# NVME.net
KiCad netlist of a schematic drawn in Altium Designer
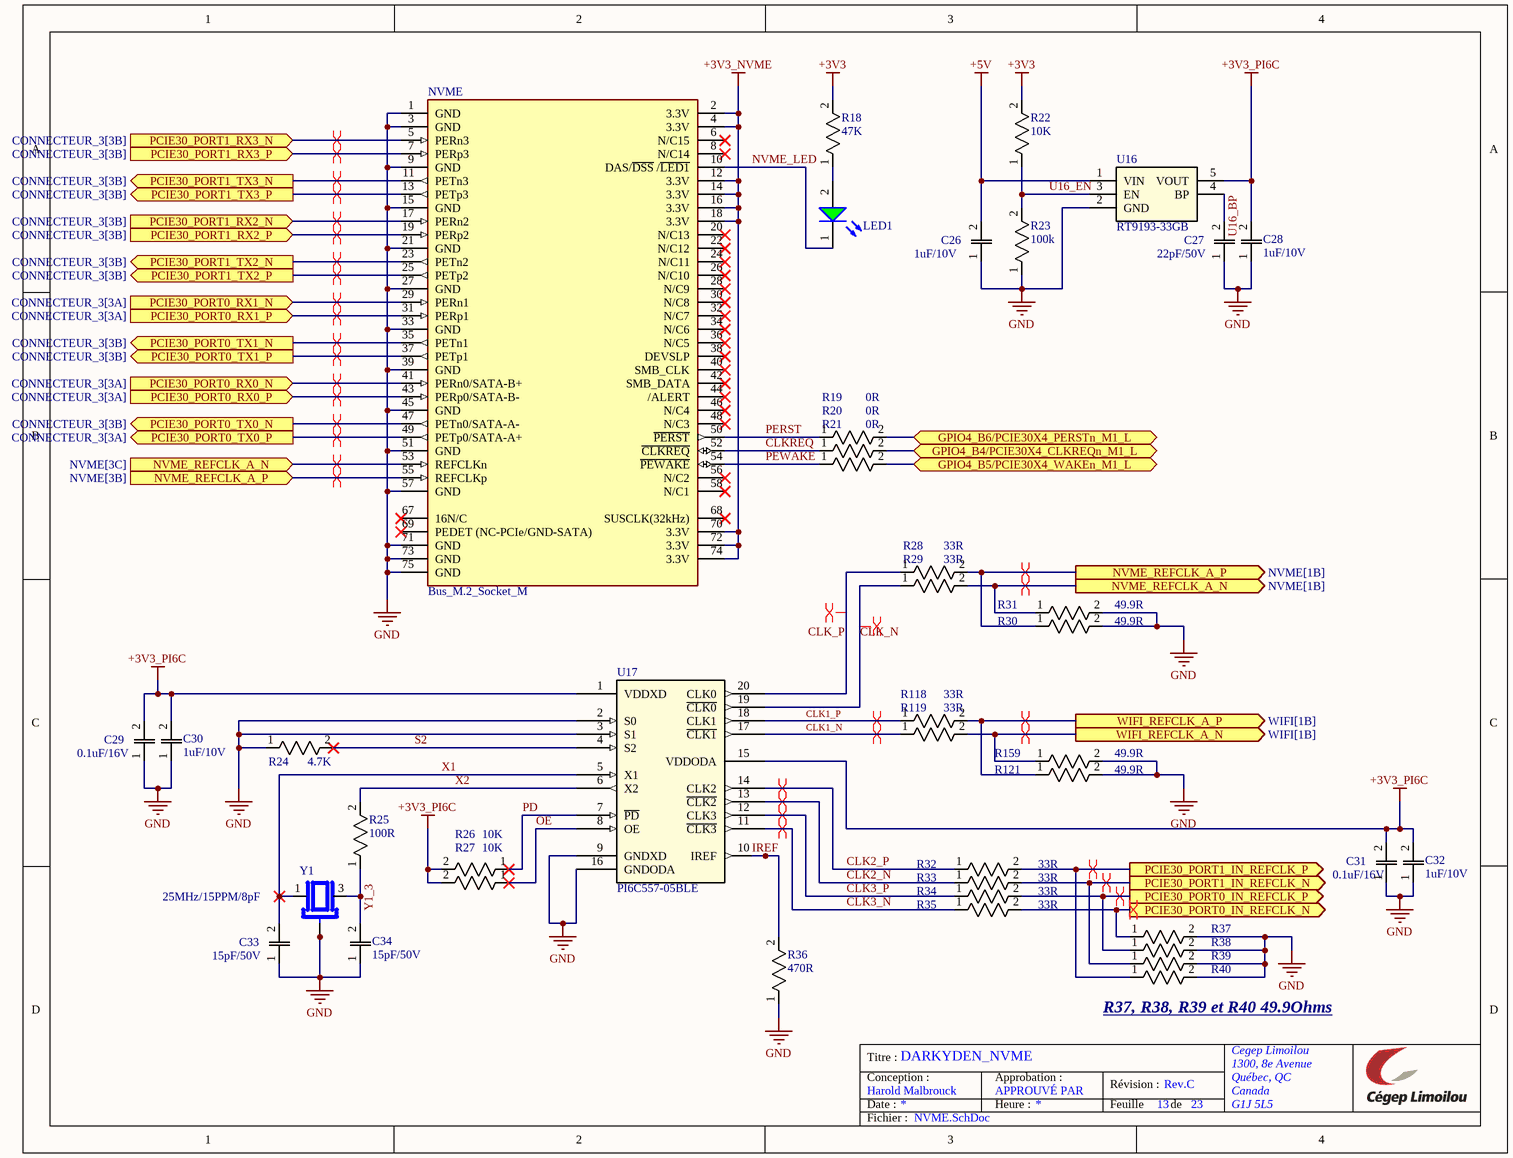
[diagram p0: NVME.SchDoc]

(export (version "E")
  (design (tool "Eeschema 10.0.6"))
  (components
    (comp (ref "C26")
      (value "1uF/10V")
      (footprint "C0805")
      (description "Multilayer Ceramic Capacitors MLCC - SMD/SMT 10V 1uF X7R 0805 10%")
      (fields
        (field (name "MANUFACTURER") "KEMET")
        (field (name "MANUFACTURER PART NUMBER") "C0805C105K8RACTU")
      )
      (libsource (lib "DARKYDEN") (part "C0805C105K8RACTU"))
    )
    (comp (ref "C27")
      (value "22pF/50V")
      (footprint "C0805")
      (description "Cap Ceramic 22pF 50V X7R 5% Pad SMD 0805 125°C T/R")
      (fields
        (field (name "MANUFACTURER") "KEMET")
        (field (name "MANUFACTURER PART NUMBER") "C0805C220J5RACTU")
      )
      (libsource (lib "DARKYDEN") (part "C0805C220J5RACTU"))
    )
    (comp (ref "C28")
      (value "1uF/10V")
      (footprint "C0805")
      (description "Multilayer Ceramic Capacitors MLCC - SMD/SMT 10V 1uF X7R 0805 10%")
      (fields
        (field (name "MANUFACTURER") "KEMET")
        (field (name "MANUFACTURER PART NUMBER") "C0805C105K8RACTU")
      )
      (libsource (lib "DARKYDEN") (part "C0805C105K8RACTU"))
    )
    (comp (ref "C29")
      (value "0.1uF/16V")
      (footprint "C0805")
      (description "0.1uF/16V ±10% X7R 0805 (2012METRIC) Ceramic Capacitor SMD Auto X7R")
      (fields
        (field (name "MANUFACTURER") "KEMET")
        (field (name "MANUFACTURER PART NUMBER") "C0805C104K4RACAUTO")
      )
      (libsource (lib "DARKYDEN") (part "C0805C104K4RACAUTO"))
    )
    (comp (ref "C30")
      (value "1uF/10V")
      (footprint "C0805")
      (description "Multilayer Ceramic Capacitors MLCC - SMD/SMT 10V 1uF X7R 0805 10%")
      (fields
        (field (name "MANUFACTURER") "KEMET")
        (field (name "MANUFACTURER PART NUMBER") "C0805C105K8RACTU")
      )
      (libsource (lib "DARKYDEN") (part "C0805C105K8RACTU"))
    )
    (comp (ref "C31")
      (value "0.1uF/16V")
      (footprint "C0805")
      (description "0.1uF/16V ±10% X7R 0805 (2012METRIC) Ceramic Capacitor SMD Auto X7R")
      (fields
        (field (name "MANUFACTURER") "KEMET")
        (field (name "MANUFACTURER PART NUMBER") "C0805C104K4RACAUTO")
      )
      (libsource (lib "DARKYDEN") (part "C0805C104K4RACAUTO"))
    )
    (comp (ref "C32")
      (value "1uF/10V")
      (footprint "C0805")
      (description "Multilayer Ceramic Capacitors MLCC - SMD/SMT 10V 1uF X7R 0805 10%")
      (fields
        (field (name "MANUFACTURER") "KEMET")
        (field (name "MANUFACTURER PART NUMBER") "C0805C105K8RACTU")
      )
      (libsource (lib "DARKYDEN") (part "C0805C105K8RACTU"))
    )
    (comp (ref "C33")
      (value "15pF/50V")
      (footprint "C0805")
      (description "Multilayer Ceramic Capacitors MLCC - SMD/SMT 50V 15pF X7R 0805 10% AEC-Q200")
      (fields
        (field (name "MANUFACTURER") "KEMET")
        (field (name "MANUFACTURER PART NUMBER") "C0805C150K5RACAUTO")
      )
      (libsource (lib "DARKYDEN") (part "C0805C150K5RACAUTO"))
    )
    (comp (ref "C34")
      (value "15pF/50V")
      (footprint "C0805")
      (description "Multilayer Ceramic Capacitors MLCC - SMD/SMT 50V 15pF X7R 0805 10% AEC-Q200")
      (fields
        (field (name "MANUFACTURER") "KEMET")
        (field (name "MANUFACTURER PART NUMBER") "C0805C150K5RACAUTO")
      )
      (libsource (lib "DARKYDEN") (part "C0805C150K5RACAUTO"))
    )
    (comp (ref "LED1")
      (value "Green, 3.2V, 140°")
      (footprint "WL-SMCD_0603")
      (description "WL-SMCD Mono-color Chip LED Diffused, SMT, size 0603, Green, 3.2V, 140°")
      (fields
        (field (name "MANUFACTURER PART NUMBER") "150060GS55040")
        (field (name "MANUFACTURER") "Wurth Elektronik")
      )
      (libsource (lib "0603_LED") (part "GREEN"))
    )
    (comp (ref "NVME")
      (value "Bus_M.2_Socket_M")
      (footprint "AMPHENOL_MDT420M03001")
      (fields (field (name "MF") "Amphenol Commercial") (field (name "MP") "MDT420M03001"))
      (libsource (lib "Bus_M.2_Socket_M") (part "Bus_M.2_Socket_M"))
    )
    (comp (ref "R18")
      (value "47K")
      (footprint "RESC1608X55N")
      (description "47K Ohm 5% 1/10W 0603 200ppm/C Molded SMD Punched Carrier T/R")
      (fields
        (field (name "MANUFACTURER") "Panasonic")
        (field (name "MANUFACTURER PART NUMBER") "ERJ-3GEYJ473V")
      )
      (libsource (lib "DARKYDEN") (part "ERJ-3GEYJ473V"))
    )
    (comp (ref "R19")
      (value "0R")
      (footprint "SamacSys:RESC1608X55N")
      (description "Zero Ohm Resistor, Jumper, 0603 [1608 Metric], Thick Film, 100 mW, 1 A, Surface Mount")
      (fields
        (field (name "MANUFACTURER_PART_NUMBER") "ERJ-3GEY0R00V")
        (field (name "MOUSER PART NUMBER") "667-ERJ-3GEY0R00V")
      )
      (libsource (lib "DARKYDEN") (part "ERJ-3GEY0R00V"))
    )
    (comp (ref "R20")
      (value "0R")
      (footprint "SamacSys:RESC1608X55N")
      (description "Zero Ohm Resistor, Jumper, 0603 [1608 Metric], Thick Film, 100 mW, 1 A, Surface Mount")
      (fields
        (field (name "MANUFACTURER_PART_NUMBER") "ERJ-3GEY0R00V")
        (field (name "MOUSER PART NUMBER") "667-ERJ-3GEY0R00V")
      )
      (libsource (lib "DARKYDEN") (part "ERJ-3GEY0R00V"))
    )
    (comp (ref "R21")
      (value "0R")
      (footprint "SamacSys:RESC1608X55N")
      (description "Zero Ohm Resistor, Jumper, 0603 [1608 Metric], Thick Film, 100 mW, 1 A, Surface Mount")
      (fields
        (field (name "MANUFACTURER_PART_NUMBER") "ERJ-3GEY0R00V")
        (field (name "MOUSER PART NUMBER") "667-ERJ-3GEY0R00V")
      )
      (libsource (lib "DARKYDEN") (part "ERJ-3GEY0R00V"))
    )
    (comp (ref "R22")
      (value "10K")
      (footprint "SamacSys:RESC1608X55N")
      (description "10K Ohm 5% Res Thick Film 0603  0.1W(1/10W) ±200ppm/C Pad SMD Automotive T/R")
      (fields
        (field (name "MANUFACTURER_PART_NUMBER") "ERJ-3GEYJ103V")
        (field (name "MOUSER PART NUMBER") "667-ERJ-3GEYJ103V")
      )
      (libsource (lib "DARKYDEN") (part "ERJ-3GEYJ103V"))
    )
    (comp (ref "R23")
      (value "100k")
      (footprint "SamacSys:RESC1608X55N")
      (description "100K Ohm 5%  Res Thick Film 0603 1/10W +/-200ppm/ßC Molded SMD Punched Carrier T/R")
      (fields
        (field (name "MANUFACTURER_PART_NUMBER") "ERJ-3GEYJ104V")
        (field (name "MOUSER PART NUMBER") "667-ERJ-3GEYJ104V")
      )
      (libsource (lib "DARKYDEN") (part "ERJ-3GEYJ104V"))
    )
    (comp (ref "R24")
      (value "4.7K")
      (footprint "RESC1608X55N")
      (description "4.7K Ohm 0.1% 0.1W 0603 ±25ppm/°C Molded SMD Punched Carrier T/R")
      (fields
        (field (name "MANUFACTURER") "Panasonic")
        (field (name "MANUFACTURER PART NUMBER") "ERA-3AEB472V")
      )
      (libsource (lib "DARKYDEN") (part "ERA-3AEB472V"))
    )
    (comp (ref "R25")
      (value "100R")
      (footprint "SamacSys:RESC1608X55N")
      (description "100 Ohm 1% 1/10W 0603 ±100ppm/°C Molded SMD Punched Carrier T/R")
      (fields
        (field (name "MANUFACTURER_PART_NUMBER") "ERJ-3EKF1000V")
        (field (name "MOUSER PART NUMBER") "667-ERJ-3EKF1000V")
      )
      (libsource (lib "DARKYDEN") (part "ERJ-3EKF1000V"))
    )
    (comp (ref "R26")
      (value "10K")
      (footprint "SamacSys:RESC1608X55N")
      (description "10K Ohm 5% Res Thick Film 0603  0.1W(1/10W) ±200ppm/C Pad SMD Automotive T/R")
      (fields
        (field (name "MANUFACTURER_PART_NUMBER") "ERJ-3GEYJ103V")
        (field (name "MOUSER PART NUMBER") "667-ERJ-3GEYJ103V")
      )
      (libsource (lib "DARKYDEN") (part "ERJ-3GEYJ103V"))
    )
    (comp (ref "R27")
      (value "10K")
      (footprint "SamacSys:RESC1608X55N")
      (description "10K Ohm 5% Res Thick Film 0603  0.1W(1/10W) ±200ppm/C Pad SMD Automotive T/R")
      (fields
        (field (name "MANUFACTURER_PART_NUMBER") "ERJ-3GEYJ103V")
        (field (name "MOUSER PART NUMBER") "667-ERJ-3GEYJ103V")
      )
      (libsource (lib "DARKYDEN") (part "ERJ-3GEYJ103V"))
    )
    (comp (ref "R28")
      (value "33R")
      (footprint "RESC1608X55N")
      (description "33 Ohm 1% 0.1W 0603 ±100ppm/°C Molded SMD Punched Carrier T/R")
      (fields
        (field (name "MANUFACTURER") "Panasonic")
        (field (name "MANUFACTURER PART NUMBER") "ERJ-3EKF33R0V")
      )
      (libsource (lib "DARKYDEN") (part "ERJ-3EKF33R0V"))
    )
    (comp (ref "R29")
      (value "33R")
      (footprint "RESC1608X55N")
      (description "33 Ohm 1% 0.1W 0603 ±100ppm/°C Molded SMD Punched Carrier T/R")
      (fields
        (field (name "MANUFACTURER") "Panasonic")
        (field (name "MANUFACTURER PART NUMBER") "ERJ-3EKF33R0V")
      )
      (libsource (lib "DARKYDEN") (part "ERJ-3EKF33R0V"))
    )
    (comp (ref "R30")
      (value "49.9R")
      (footprint "RESC1608X55N")
      (description "100Mw Thick Film Resistors 100Ppm/ 1% 49.9 0603 Chip Resistor Surface Mount Rohs")
      (fields
        (field (name "MANUFACTURER") "Panasonic")
        (field (name "MANUFACTURER PART NUMBER") "ERJ-3EKF49R9V")
      )
      (libsource (lib "DARKYDEN") (part "ERJ-3EKF49R9V"))
    )
    (comp (ref "R31")
      (value "49.9R")
      (footprint "RESC1608X55N")
      (description "100Mw Thick Film Resistors 100Ppm/ 1% 49.9 0603 Chip Resistor Surface Mount Rohs")
      (fields
        (field (name "MANUFACTURER") "Panasonic")
        (field (name "MANUFACTURER PART NUMBER") "ERJ-3EKF49R9V")
      )
      (libsource (lib "DARKYDEN") (part "ERJ-3EKF49R9V"))
    )
    (comp (ref "R32")
      (value "33R")
      (footprint "RESC1608X55N")
      (description "33 Ohm 1% 0.1W 0603 ±100ppm/°C Molded SMD Punched Carrier T/R")
      (fields
        (field (name "MANUFACTURER") "Panasonic")
        (field (name "MANUFACTURER PART NUMBER") "ERJ-3EKF33R0V")
      )
      (libsource (lib "DARKYDEN") (part "ERJ-3EKF33R0V"))
    )
    (comp (ref "R33")
      (value "33R")
      (footprint "RESC1608X55N")
      (description "33 Ohm 1% 0.1W 0603 ±100ppm/°C Molded SMD Punched Carrier T/R")
      (fields
        (field (name "MANUFACTURER") "Panasonic")
        (field (name "MANUFACTURER PART NUMBER") "ERJ-3EKF33R0V")
      )
      (libsource (lib "DARKYDEN") (part "ERJ-3EKF33R0V"))
    )
    (comp (ref "R34")
      (value "33R")
      (footprint "RESC1608X55N")
      (description "33 Ohm 1% 0.1W 0603 ±100ppm/°C Molded SMD Punched Carrier T/R")
      (fields
        (field (name "MANUFACTURER") "Panasonic")
        (field (name "MANUFACTURER PART NUMBER") "ERJ-3EKF33R0V")
      )
      (libsource (lib "DARKYDEN") (part "ERJ-3EKF33R0V"))
    )
    (comp (ref "R35")
      (value "33R")
      (footprint "RESC1608X55N")
      (description "33 Ohm 1% 0.1W 0603 ±100ppm/°C Molded SMD Punched Carrier T/R")
      (fields
        (field (name "MANUFACTURER") "Panasonic")
        (field (name "MANUFACTURER PART NUMBER") "ERJ-3EKF33R0V")
      )
      (libsource (lib "DARKYDEN") (part "ERJ-3EKF33R0V"))
    )
    (comp (ref "R36")
      (value "470R")
      (footprint "RESC1608X55N")
      (description "470 Ohm 5% 1/10W 0603 +/-200ppm/ßC Molded SMD Punched Carrier T/R")
      (fields
        (field (name "MANUFACTURER") "Panasonic")
        (field (name "MANUFACTURER PART NUMBER") "ERJ-3GEYJ471V")
      )
      (libsource (lib "DARKYDEN") (part "ERJ-3GEYJ471V"))
    )
    (comp (ref "R37")
      (value "49.9R")
      (footprint "RESC1608X55N")
      (description "100Mw Thick Film Resistors 100Ppm/ 1% 49.9 0603 Chip Resistor Surface Mount Rohs")
      (fields
        (field (name "MANUFACTURER") "Panasonic")
        (field (name "MANUFACTURER PART NUMBER") "ERJ-3EKF49R9V")
      )
      (libsource (lib "DARKYDEN") (part "ERJ-3EKF49R9V"))
    )
    (comp (ref "R38")
      (value "49.9R")
      (footprint "RESC1608X55N")
      (description "100Mw Thick Film Resistors 100Ppm/ 1% 49.9 0603 Chip Resistor Surface Mount Rohs")
      (fields
        (field (name "MANUFACTURER") "Panasonic")
        (field (name "MANUFACTURER PART NUMBER") "ERJ-3EKF49R9V")
      )
      (libsource (lib "DARKYDEN") (part "ERJ-3EKF49R9V"))
    )
    (comp (ref "R39")
      (value "49.9R")
      (footprint "RESC1608X55N")
      (description "100Mw Thick Film Resistors 100Ppm/ 1% 49.9 0603 Chip Resistor Surface Mount Rohs")
      (fields
        (field (name "MANUFACTURER") "Panasonic")
        (field (name "MANUFACTURER PART NUMBER") "ERJ-3EKF49R9V")
      )
      (libsource (lib "DARKYDEN") (part "ERJ-3EKF49R9V"))
    )
    (comp (ref "R40")
      (value "49.9R")
      (footprint "RESC1608X55N")
      (description "100Mw Thick Film Resistors 100Ppm/ 1% 49.9 0603 Chip Resistor Surface Mount Rohs")
      (fields
        (field (name "MANUFACTURER") "Panasonic")
        (field (name "MANUFACTURER PART NUMBER") "ERJ-3EKF49R9V")
      )
      (libsource (lib "DARKYDEN") (part "ERJ-3EKF49R9V"))
    )
    (comp (ref "R118")
      (value "33R")
      (footprint "RESC1608X55N")
      (description "33 Ohm 1% 0.1W 0603 ±100ppm/°C Molded SMD Punched Carrier T/R")
      (fields
        (field (name "MANUFACTURER") "Panasonic")
        (field (name "MANUFACTURER PART NUMBER") "ERJ-3EKF33R0V")
      )
      (libsource (lib "DARKYDEN") (part "ERJ-3EKF33R0V"))
    )
    (comp (ref "R119")
      (value "33R")
      (footprint "RESC1608X55N")
      (description "33 Ohm 1% 0.1W 0603 ±100ppm/°C Molded SMD Punched Carrier T/R")
      (fields
        (field (name "MANUFACTURER") "Panasonic")
        (field (name "MANUFACTURER PART NUMBER") "ERJ-3EKF33R0V")
      )
      (libsource (lib "DARKYDEN") (part "ERJ-3EKF33R0V"))
    )
    (comp (ref "R121")
      (value "49.9R")
      (footprint "RESC1608X55N")
      (description "100Mw Thick Film Resistors 100Ppm/ 1% 49.9 0603 Chip Resistor Surface Mount Rohs")
      (fields
        (field (name "MANUFACTURER") "Panasonic")
        (field (name "MANUFACTURER PART NUMBER") "ERJ-3EKF49R9V")
      )
      (libsource (lib "DARKYDEN") (part "ERJ-3EKF49R9V"))
    )
    (comp (ref "R159")
      (value "49.9R")
      (footprint "RESC1608X55N")
      (description "100Mw Thick Film Resistors 100Ppm/ 1% 49.9 0603 Chip Resistor Surface Mount Rohs")
      (fields
        (field (name "MANUFACTURER") "Panasonic")
        (field (name "MANUFACTURER PART NUMBER") "ERJ-3EKF49R9V")
      )
      (libsource (lib "DARKYDEN") (part "ERJ-3EKF49R9V"))
    )
    (comp (ref "U16")
      (value "RT9193-33GB")
      (footprint "SOT-23-5_RIT")
      (description "RT9193 Series 300 mA 3.3 V Ultra-Low Noise Ultra-Fast CMOS LDO Regulator-SC-70-5")
      (fields (field (name "MANUFACTURER") "Richtek"))
      (libsource (lib "DARKYDEN") (part "RT9193-33GB"))
    )
    (comp (ref "U17")
      (value "PI6C557-05BLE")
      (footprint "L20_PER-M")
      (description "Clock Generators & Support Products PCI express Gen 2 4 output clock gen")
      (fields (field (name "MANUFACTURER") "Diodes"))
      (libsource (lib "PI6C557-05BLE") (part "PI6C557-05BLE"))
    )
    (comp (ref "Y1")
      (value "25MHz/15PPM/8pF")
      (footprint "XTAL_ECS-250-8-37B2-RWY-TR")
      (description "Crystal 25MHz ±15ppm (Tol) ±15ppm (Stability) 8pF FUND 50Ohm 4-Pin Mini-CSMD T/R")
      (fields (field (name "MF") "{'manufacturer': u'ECS Inc.'}") (field (name "MP") "ECS-250-8-37B2-RWY-TR"))
      (libsource (lib "ECS-250-8-37B2-RWY-TR") (part "ECS-250-8-37B2-RWY-TR"))
    )
  )
  (nets
    (net (code "1") (name "+3V3") (class "Default")
      (node (ref "R18") (pin "2") (pinfunction "2_2") (pintype "passive"))
      (node (ref "R22") (pin "2") (pinfunction "2_2") (pintype "passive"))
    )
    (net (code "2") (name "+3V3_NVME") (class "Default")
      (node (ref "NVME") (pin "12") (pinfunction "3.3V_12") (pintype "power_in"))
      (node (ref "NVME") (pin "14") (pinfunction "3.3V_14") (pintype "power_in"))
      (node (ref "NVME") (pin "16") (pinfunction "3.3V_16") (pintype "power_in"))
      (node (ref "NVME") (pin "18") (pinfunction "3.3V_18") (pintype "power_in"))
      (node (ref "NVME") (pin "2") (pinfunction "3.3V_2") (pintype "power_in"))
      (node (ref "NVME") (pin "4") (pinfunction "3.3V_4") (pintype "power_in"))
      (node (ref "NVME") (pin "70") (pinfunction "3.3V_70") (pintype "power_in"))
      (node (ref "NVME") (pin "72") (pinfunction "3.3V_72") (pintype "power_in"))
      (node (ref "NVME") (pin "74") (pinfunction "3.3V_74") (pintype "power_in"))
    )
    (net (code "3") (name "+3V3_PI6C") (class "Default")
      (node (ref "C28") (pin "2") (pinfunction "2_2") (pintype "passive"))
      (node (ref "C29") (pin "2") (pinfunction "2_2") (pintype "passive"))
      (node (ref "C30") (pin "2") (pinfunction "2_2") (pintype "passive"))
      (node (ref "C31") (pin "2") (pinfunction "2_2") (pintype "passive"))
      (node (ref "C32") (pin "2") (pinfunction "2_2") (pintype "passive"))
      (node (ref "R26") (pin "2") (pinfunction "2_2") (pintype "passive"))
      (node (ref "R27") (pin "2") (pinfunction "2_2") (pintype "passive"))
      (node (ref "U16") (pin "5") (pinfunction "VOUT_5") (pintype "power_in"))
      (node (ref "U17") (pin "1") (pinfunction "VDDXD_1") (pintype "power_in"))
      (node (ref "U17") (pin "15") (pinfunction "VDDODA_15") (pintype "power_in"))
    )
    (net (code "4") (name "+5V") (class "Default")
      (node (ref "C26") (pin "2") (pinfunction "2_2") (pintype "passive"))
      (node (ref "U16") (pin "1") (pinfunction "VIN_1") (pintype "power_in"))
    )
    (net (code "5") (name "/CLK1_N") (class "Default")
      (node (ref "R119") (pin "1") (pinfunction "1_1") (pintype "passive"))
      (node (ref "U17") (pin "17") (pinfunction "~{CLK1}_17") (pintype "output"))
    )
    (net (code "6") (name "/CLK1_P") (class "Default")
      (node (ref "R118") (pin "1") (pinfunction "1_1") (pintype "passive"))
      (node (ref "U17") (pin "18") (pinfunction "CLK1_18") (pintype "output"))
    )
    (net (code "7") (name "/CLK2_N") (class "Default")
      (node (ref "R33") (pin "1") (pinfunction "1_1") (pintype "passive"))
      (node (ref "U17") (pin "13") (pinfunction "~{CLK2}_13") (pintype "output"))
    )
    (net (code "8") (name "/CLK2_P") (class "Default")
      (node (ref "R32") (pin "1") (pinfunction "1_1") (pintype "passive"))
      (node (ref "U17") (pin "14") (pinfunction "CLK2_14") (pintype "output"))
    )
    (net (code "9") (name "/CLK3_N") (class "Default")
      (node (ref "R35") (pin "1") (pinfunction "1_1") (pintype "passive"))
      (node (ref "U17") (pin "11") (pinfunction "~{CLK3}_11") (pintype "output"))
    )
    (net (code "10") (name "/CLK3_P") (class "Default")
      (node (ref "R34") (pin "1") (pinfunction "1_1") (pintype "passive"))
      (node (ref "U17") (pin "12") (pinfunction "CLK3_12") (pintype "output"))
    )
    (net (code "11") (name "/CLKREQ") (class "Default")
      (node (ref "NVME") (pin "52") (pinfunction "~{CLKREQ}_52") (pintype "bidirectional"))
      (node (ref "R20") (pin "1") (pinfunction "1_1") (pintype "passive"))
    )
    (net (code "12") (name "/CLK_N") (class "Default")
      (node (ref "R29") (pin "1") (pinfunction "1_1") (pintype "passive"))
      (node (ref "U17") (pin "19") (pinfunction "~{CLK0}_19") (pintype "output"))
    )
    (net (code "13") (name "/CLK_P") (class "Default")
      (node (ref "R28") (pin "1") (pinfunction "1_1") (pintype "passive"))
      (node (ref "U17") (pin "20") (pinfunction "CLK0_20") (pintype "output"))
    )
    (net (code "14") (name "/GPIO4_B4{slash}PCIE30X4_CLKREQn_M1_L") (class "Default")
      (node (ref "R20") (pin "2") (pinfunction "2_2") (pintype "passive"))
    )
    (net (code "15") (name "/GPIO4_B5{slash}PCIE30X4_WAKEn_M1_L") (class "Default")
      (node (ref "R21") (pin "2") (pinfunction "2_2") (pintype "passive"))
    )
    (net (code "16") (name "/GPIO4_B6{slash}PCIE30X4_PERSTn_M1_L") (class "Default")
      (node (ref "R19") (pin "2") (pinfunction "2_2") (pintype "passive"))
    )
    (net (code "17") (name "/IREF") (class "Default")
      (node (ref "R36") (pin "2") (pinfunction "2_2") (pintype "passive"))
      (node (ref "U17") (pin "10") (pinfunction "IREF_10") (pintype "output"))
    )
    (net (code "18") (name "/NVME_LED") (class "Default")
      (node (ref "LED1") (pin "1") (pinfunction "K_1") (pintype "passive"))
      (node (ref "NVME") (pin "10") (pinfunction "DAS/~{DSS}_/~{LED1}_10") (pintype "passive"))
    )
    (net (code "19") (name "/NVME_REFCLK_A_N") (class "Default")
      (node (ref "NVME") (pin "53") (pinfunction "REFCLKn_53") (pintype "input"))
      (node (ref "R29") (pin "2") (pinfunction "2_2") (pintype "passive"))
      (node (ref "R31") (pin "1") (pinfunction "1_1") (pintype "passive"))
    )
    (net (code "20") (name "/NVME_REFCLK_A_P") (class "Default")
      (node (ref "NVME") (pin "55") (pinfunction "REFCLKp_55") (pintype "input"))
      (node (ref "R28") (pin "2") (pinfunction "2_2") (pintype "passive"))
      (node (ref "R30") (pin "1") (pinfunction "1_1") (pintype "passive"))
    )
    (net (code "21") (name "/OE") (class "Default")
      (node (ref "R27") (pin "1") (pinfunction "1_1") (pintype "passive"))
      (node (ref "U17") (pin "8") (pinfunction "OE_8") (pintype "input"))
    )
    (net (code "22") (name "/PCIE30_PORT0_IN_REFCLK_N") (class "Default")
      (node (ref "R35") (pin "2") (pinfunction "2_2") (pintype "passive"))
      (node (ref "R37") (pin "1") (pinfunction "1_1") (pintype "passive"))
    )
    (net (code "23") (name "/PCIE30_PORT0_IN_REFCLK_P") (class "Default")
      (node (ref "R34") (pin "2") (pinfunction "2_2") (pintype "passive"))
      (node (ref "R38") (pin "1") (pinfunction "1_1") (pintype "passive"))
    )
    (net (code "24") (name "/PCIE30_PORT0_RX0_N") (class "Default")
      (node (ref "NVME") (pin "41") (pinfunction "PERn0/SATA-B+_41") (pintype "input"))
    )
    (net (code "25") (name "/PCIE30_PORT0_RX0_P") (class "Default")
      (node (ref "NVME") (pin "43") (pinfunction "PERp0/SATA-B-_43") (pintype "input"))
    )
    (net (code "26") (name "/PCIE30_PORT0_RX1_N") (class "Default")
      (node (ref "NVME") (pin "29") (pinfunction "PERn1_29") (pintype "input"))
    )
    (net (code "27") (name "/PCIE30_PORT0_RX1_P") (class "Default")
      (node (ref "NVME") (pin "31") (pinfunction "PERp1_31") (pintype "input"))
    )
    (net (code "28") (name "/PCIE30_PORT0_TX0_N") (class "Default")
      (node (ref "NVME") (pin "47") (pinfunction "PETn0/SATA-A-_47") (pintype "output"))
    )
    (net (code "29") (name "/PCIE30_PORT0_TX0_P") (class "Default")
      (node (ref "NVME") (pin "49") (pinfunction "PETp0/SATA-A+_49") (pintype "output"))
    )
    (net (code "30") (name "/PCIE30_PORT0_TX1_N") (class "Default")
      (node (ref "NVME") (pin "35") (pinfunction "PETn1_35") (pintype "output"))
    )
    (net (code "31") (name "/PCIE30_PORT0_TX1_P") (class "Default")
      (node (ref "NVME") (pin "37") (pinfunction "PETp1_37") (pintype "output"))
    )
    (net (code "32") (name "/PCIE30_PORT1_IN_REFCLK_N") (class "Default")
      (node (ref "R33") (pin "2") (pinfunction "2_2") (pintype "passive"))
      (node (ref "R39") (pin "1") (pinfunction "1_1") (pintype "passive"))
    )
    (net (code "33") (name "/PCIE30_PORT1_IN_REFCLK_P") (class "Default")
      (node (ref "R32") (pin "2") (pinfunction "2_2") (pintype "passive"))
      (node (ref "R40") (pin "1") (pinfunction "1_1") (pintype "passive"))
    )
    (net (code "34") (name "/PCIE30_PORT1_RX2_N") (class "Default")
      (node (ref "NVME") (pin "17") (pinfunction "PERn2_17") (pintype "input"))
    )
    (net (code "35") (name "/PCIE30_PORT1_RX2_P") (class "Default")
      (node (ref "NVME") (pin "19") (pinfunction "PERp2_19") (pintype "input"))
    )
    (net (code "36") (name "/PCIE30_PORT1_RX3_N") (class "Default")
      (node (ref "NVME") (pin "5") (pinfunction "PERn3_5") (pintype "input"))
    )
    (net (code "37") (name "/PCIE30_PORT1_RX3_P") (class "Default")
      (node (ref "NVME") (pin "7") (pinfunction "PERp3_7") (pintype "input"))
    )
    (net (code "38") (name "/PCIE30_PORT1_TX2_N") (class "Default")
      (node (ref "NVME") (pin "23") (pinfunction "PETn2_23") (pintype "output"))
    )
    (net (code "39") (name "/PCIE30_PORT1_TX2_P") (class "Default")
      (node (ref "NVME") (pin "25") (pinfunction "PETp2_25") (pintype "output"))
    )
    (net (code "40") (name "/PCIE30_PORT1_TX3_N") (class "Default")
      (node (ref "NVME") (pin "11") (pinfunction "PETn3_11") (pintype "output"))
    )
    (net (code "41") (name "/PCIE30_PORT1_TX3_P") (class "Default")
      (node (ref "NVME") (pin "13") (pinfunction "PETp3_13") (pintype "output"))
    )
    (net (code "42") (name "/PD") (class "Default")
      (node (ref "R26") (pin "1") (pinfunction "1_1") (pintype "passive"))
      (node (ref "U17") (pin "7") (pinfunction "~{PD}_7") (pintype "input"))
    )
    (net (code "43") (name "/PERST") (class "Default")
      (node (ref "NVME") (pin "50") (pinfunction "~{PERST}_50") (pintype "output"))
      (node (ref "R19") (pin "1") (pinfunction "1_1") (pintype "passive"))
    )
    (net (code "44") (name "/PEWAKE") (class "Default")
      (node (ref "NVME") (pin "54") (pinfunction "~{PEWAKE}_54") (pintype "bidirectional"))
      (node (ref "R21") (pin "1") (pinfunction "1_1") (pintype "passive"))
    )
    (net (code "45") (name "/S2") (class "Default")
      (node (ref "R24") (pin "2") (pinfunction "2_2") (pintype "passive"))
      (node (ref "U17") (pin "4") (pinfunction "S2_4") (pintype "input"))
    )
    (net (code "46") (name "/U16_BP") (class "Default")
      (node (ref "C27") (pin "2") (pinfunction "2_2") (pintype "passive"))
      (node (ref "U16") (pin "4") (pinfunction "BP_4") (pintype "passive"))
    )
    (net (code "47") (name "/U16_EN") (class "Default")
      (node (ref "R22") (pin "1") (pinfunction "1_1") (pintype "passive"))
      (node (ref "R23") (pin "2") (pinfunction "2_2") (pintype "passive"))
      (node (ref "U16") (pin "3") (pinfunction "EN_3") (pintype "passive"))
    )
    (net (code "48") (name "/WIFI_REFCLK_A_N") (class "Default")
      (node (ref "R119") (pin "2") (pinfunction "2_2") (pintype "passive"))
      (node (ref "R159") (pin "1") (pinfunction "1_1") (pintype "passive"))
    )
    (net (code "49") (name "/WIFI_REFCLK_A_P") (class "Default")
      (node (ref "R118") (pin "2") (pinfunction "2_2") (pintype "passive"))
      (node (ref "R121") (pin "1") (pinfunction "1_1") (pintype "passive"))
    )
    (net (code "50") (name "/X1") (class "Default")
      (node (ref "C33") (pin "2") (pinfunction "2_2") (pintype "passive"))
      (node (ref "U17") (pin "5") (pinfunction "X1_5") (pintype "input"))
      (node (ref "Y1") (pin "1") (pinfunction "IN/OUT_1") (pintype "passive"))
    )
    (net (code "51") (name "/X2") (class "Default")
      (node (ref "R25") (pin "2") (pinfunction "2_2") (pintype "passive"))
      (node (ref "U17") (pin "6") (pinfunction "X2_6") (pintype "output"))
    )
    (net (code "52") (name "/Y1_3") (class "Default")
      (node (ref "C34") (pin "2") (pinfunction "2_2") (pintype "passive"))
      (node (ref "R25") (pin "1") (pinfunction "1_1") (pintype "passive"))
      (node (ref "Y1") (pin "3") (pinfunction "OUT/IN_3") (pintype "passive"))
    )
    (net (code "53") (name "GND") (class "Default")
      (node (ref "C26") (pin "1") (pinfunction "1_1") (pintype "passive"))
      (node (ref "C27") (pin "1") (pinfunction "1_1") (pintype "passive"))
      (node (ref "C28") (pin "1") (pinfunction "1_1") (pintype "passive"))
      (node (ref "C29") (pin "1") (pinfunction "1_1") (pintype "passive"))
      (node (ref "C30") (pin "1") (pinfunction "1_1") (pintype "passive"))
      (node (ref "C31") (pin "1") (pinfunction "1_1") (pintype "passive"))
      (node (ref "C32") (pin "1") (pinfunction "1_1") (pintype "passive"))
      (node (ref "C33") (pin "1") (pinfunction "1_1") (pintype "passive"))
      (node (ref "C34") (pin "1") (pinfunction "1_1") (pintype "passive"))
      (node (ref "NVME") (pin "1") (pinfunction "GND_1") (pintype "passive"))
      (node (ref "NVME") (pin "15") (pinfunction "GND_15") (pintype "passive"))
      (node (ref "NVME") (pin "21") (pinfunction "GND_21") (pintype "passive"))
      (node (ref "NVME") (pin "27") (pinfunction "GND_27") (pintype "passive"))
      (node (ref "NVME") (pin "3") (pinfunction "GND_3") (pintype "passive"))
      (node (ref "NVME") (pin "33") (pinfunction "GND_33") (pintype "passive"))
      (node (ref "NVME") (pin "39") (pinfunction "GND_39") (pintype "passive"))
      (node (ref "NVME") (pin "45") (pinfunction "GND_45") (pintype "passive"))
      (node (ref "NVME") (pin "51") (pinfunction "GND_51") (pintype "passive"))
      (node (ref "NVME") (pin "57") (pinfunction "GND_57") (pintype "passive"))
      (node (ref "NVME") (pin "71") (pinfunction "GND_71") (pintype "passive"))
      (node (ref "NVME") (pin "73") (pinfunction "GND_73") (pintype "passive"))
      (node (ref "NVME") (pin "75") (pinfunction "GND_75") (pintype "passive"))
      (node (ref "NVME") (pin "9") (pinfunction "GND_9") (pintype "passive"))
      (node (ref "R121") (pin "2") (pinfunction "2_2") (pintype "passive"))
      (node (ref "R159") (pin "2") (pinfunction "2_2") (pintype "passive"))
      (node (ref "R23") (pin "1") (pinfunction "1_1") (pintype "passive"))
      (node (ref "R24") (pin "1") (pinfunction "1_1") (pintype "passive"))
      (node (ref "R30") (pin "2") (pinfunction "2_2") (pintype "passive"))
      (node (ref "R31") (pin "2") (pinfunction "2_2") (pintype "passive"))
      (node (ref "R36") (pin "1") (pinfunction "1_1") (pintype "passive"))
      (node (ref "R37") (pin "2") (pinfunction "2_2") (pintype "passive"))
      (node (ref "R38") (pin "2") (pinfunction "2_2") (pintype "passive"))
      (node (ref "R39") (pin "2") (pinfunction "2_2") (pintype "passive"))
      (node (ref "R40") (pin "2") (pinfunction "2_2") (pintype "passive"))
      (node (ref "U16") (pin "2") (pinfunction "GND_2") (pintype "passive"))
      (node (ref "U17") (pin "16") (pinfunction "GNDODA_16") (pintype "passive"))
      (node (ref "U17") (pin "2") (pinfunction "S0_2") (pintype "input"))
      (node (ref "U17") (pin "3") (pinfunction "S1_3") (pintype "input"))
      (node (ref "U17") (pin "9") (pinfunction "GNDXD_9") (pintype "passive"))
      (node (ref "Y1") (pin "2") (pinfunction "GND_2") (pintype "power_in"))
      (node (ref "Y1") (pin "4") (pinfunction "GND_4") (pintype "power_in"))
    )
    (net (code "54") (name "Net-(LED1-A)") (class "Default")
      (node (ref "LED1") (pin "2") (pinfunction "A_2") (pintype "passive"))
      (node (ref "R18") (pin "1") (pinfunction "1_1") (pintype "passive"))
    )
    (net (code "55") (name "unconnected-(NVME-16N{slash}C-Pad67)") (class "Default")
      (node (ref "NVME") (pin "67") (pinfunction "16N/C_67") (pintype "passive+no_connect"))
    )
    (net (code "56") (name "unconnected-(NVME-DEVSLP-Pad38)") (class "Default")
      (node (ref "NVME") (pin "38") (pinfunction "DEVSLP_38") (pintype "passive+no_connect"))
    )
    (net (code "57") (name "unconnected-(NVME-N{slash}C1-Pad58)") (class "Default")
      (node (ref "NVME") (pin "58") (pinfunction "N/C1_58") (pintype "passive+no_connect"))
    )
    (net (code "58") (name "unconnected-(NVME-N{slash}C2-Pad56)") (class "Default")
      (node (ref "NVME") (pin "56") (pinfunction "N/C2_56") (pintype "passive+no_connect"))
    )
    (net (code "59") (name "unconnected-(NVME-N{slash}C3-Pad48)") (class "Default")
      (node (ref "NVME") (pin "48") (pinfunction "N/C3_48") (pintype "passive+no_connect"))
    )
    (net (code "60") (name "unconnected-(NVME-N{slash}C4-Pad46)") (class "Default")
      (node (ref "NVME") (pin "46") (pinfunction "N/C4_46") (pintype "passive+no_connect"))
    )
    (net (code "61") (name "unconnected-(NVME-N{slash}C5-Pad36)") (class "Default")
      (node (ref "NVME") (pin "36") (pinfunction "N/C5_36") (pintype "passive+no_connect"))
    )
    (net (code "62") (name "unconnected-(NVME-N{slash}C6-Pad34)") (class "Default")
      (node (ref "NVME") (pin "34") (pinfunction "N/C6_34") (pintype "passive+no_connect"))
    )
    (net (code "63") (name "unconnected-(NVME-N{slash}C7-Pad32)") (class "Default")
      (node (ref "NVME") (pin "32") (pinfunction "N/C7_32") (pintype "passive+no_connect"))
    )
    (net (code "64") (name "unconnected-(NVME-N{slash}C8-Pad30)") (class "Default")
      (node (ref "NVME") (pin "30") (pinfunction "N/C8_30") (pintype "passive+no_connect"))
    )
    (net (code "65") (name "unconnected-(NVME-N{slash}C9-Pad28)") (class "Default")
      (node (ref "NVME") (pin "28") (pinfunction "N/C9_28") (pintype "passive+no_connect"))
    )
    (net (code "66") (name "unconnected-(NVME-N{slash}C10-Pad26)") (class "Default")
      (node (ref "NVME") (pin "26") (pinfunction "N/C10_26") (pintype "passive+no_connect"))
    )
    (net (code "67") (name "unconnected-(NVME-N{slash}C11-Pad24)") (class "Default")
      (node (ref "NVME") (pin "24") (pinfunction "N/C11_24") (pintype "passive+no_connect"))
    )
    (net (code "68") (name "unconnected-(NVME-N{slash}C12-Pad22)") (class "Default")
      (node (ref "NVME") (pin "22") (pinfunction "N/C12_22") (pintype "passive+no_connect"))
    )
    (net (code "69") (name "unconnected-(NVME-N{slash}C13-Pad20)") (class "Default")
      (node (ref "NVME") (pin "20") (pinfunction "N/C13_20") (pintype "passive+no_connect"))
    )
    (net (code "70") (name "unconnected-(NVME-N{slash}C14-Pad8)") (class "Default")
      (node (ref "NVME") (pin "8") (pinfunction "N/C14_8") (pintype "passive+no_connect"))
    )
    (net (code "71") (name "unconnected-(NVME-N{slash}C15-Pad6)") (class "Default")
      (node (ref "NVME") (pin "6") (pinfunction "N/C15_6") (pintype "passive+no_connect"))
    )
    (net (code "72") (name "unconnected-(NVME-PEDET_(NC-PCIe{slash}GND-SATA)-Pad69)") (class "Default")
      (node (ref "NVME") (pin "69") (pinfunction "PEDET_(NC-PCIe/GND-SATA)_69") (pintype "passive+no_connect"))
    )
    (net (code "73") (name "unconnected-(NVME-SMB_CLK-Pad40)") (class "Default")
      (node (ref "NVME") (pin "40") (pinfunction "SMB_CLK_40") (pintype "passive+no_connect"))
    )
    (net (code "74") (name "unconnected-(NVME-SMB_DATA-Pad42)") (class "Default")
      (node (ref "NVME") (pin "42") (pinfunction "SMB_DATA_42") (pintype "passive+no_connect"))
    )
    (net (code "75") (name "unconnected-(NVME-SUSCLK(32kHz)-Pad68)") (class "Default")
      (node (ref "NVME") (pin "68") (pinfunction "SUSCLK(32kHz)_68") (pintype "passive+no_connect"))
    )
    (net (code "76") (name "unconnected-(NVME-{slash}ALERT-Pad44)") (class "Default")
      (node (ref "NVME") (pin "44") (pinfunction "/ALERT_44") (pintype "passive+no_connect"))
    )
  )
)
